# TSAL-GLV.net
KiCad netlist of a schematic drawn in EAGLE
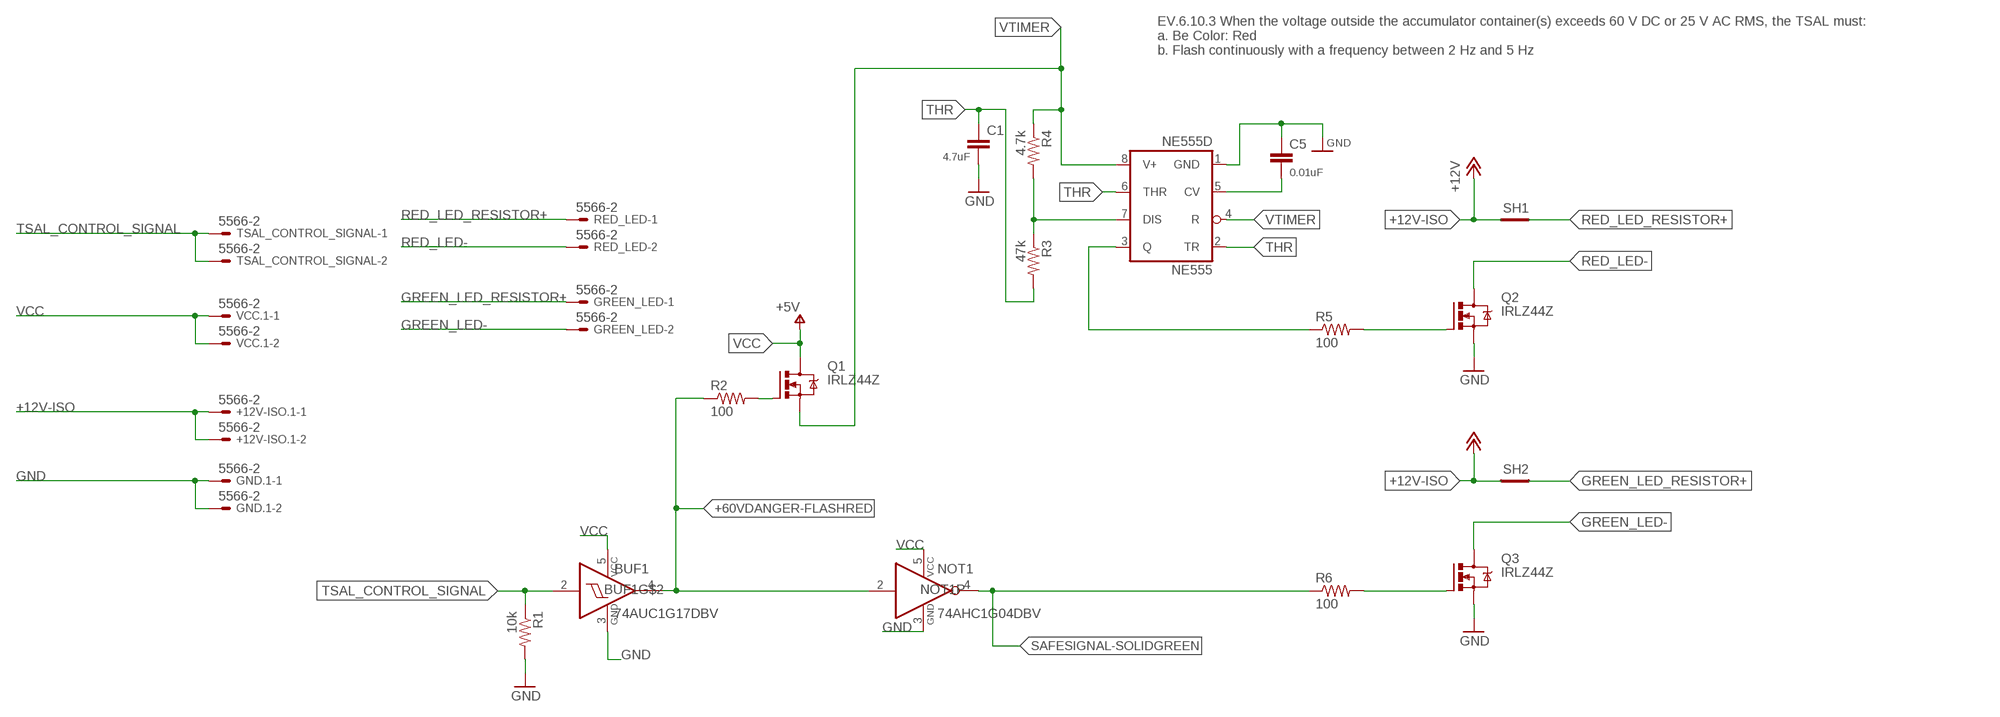
[diagram p0: schematic, sheet 1]

(export (version "E")
  (design (tool "Eeschema 10.0.6"))
  (components
    (comp (ref "+12V-ISO.1")
      (value "5566-2")
      (footprint "eagle-import:5566-2")
      (fields (field (name "MF") "MOLEX"))
      (libsource (lib "eagle-import") (part "5566-2"))
    )
    (comp (ref "BUF1")
      (value "74AUC1G17DBV")
      (footprint "eagle-import:SOT23-5")
      (libsource (lib "eagle-import") (part "741G17DBVAUC"))
    )
    (comp (ref "C1")
      (value "4.7uF")
      (footprint "eagle-import:C0805")
      (libsource (lib "eagle-import") (part "C-EUC0805"))
    )
    (comp (ref "C5")
      (value "0.01uF")
      (footprint "eagle-import:C0805")
      (libsource (lib "eagle-import") (part "C-EUC0805"))
    )
    (comp (ref "GND.1")
      (value "5566-2")
      (footprint "eagle-import:5566-2")
      (fields (field (name "MF") "MOLEX"))
      (libsource (lib "eagle-import") (part "5566-2"))
    )
    (comp (ref "GREEN_LED")
      (value "5566-2")
      (footprint "eagle-import:5566-2")
      (fields (field (name "MF") "MOLEX"))
      (libsource (lib "eagle-import") (part "5566-2"))
    )
    (comp (ref "NE555")
      (value "NE555D")
      (footprint "eagle-import:SO08")
      (libsource (lib "eagle-import") (part "555DNE"))
    )
    (comp (ref "NOT1")
      (value "74AHC1G04DBV")
      (footprint "eagle-import:SOT23-5")
      (libsource (lib "eagle-import") (part "741G04DBVAHC"))
    )
    (comp (ref "Q1")
      (value "IRLZ44Z")
      (footprint "eagle-import:TO220BH")
      (libsource (lib "eagle-import") (part "IRLZ44Z"))
    )
    (comp (ref "Q2")
      (value "IRLZ44Z")
      (footprint "eagle-import:TO220BH")
      (libsource (lib "eagle-import") (part "IRLZ44Z"))
    )
    (comp (ref "Q3")
      (value "IRLZ44Z")
      (footprint "eagle-import:TO220BH")
      (libsource (lib "eagle-import") (part "IRLZ44Z"))
    )
    (comp (ref "R1")
      (value "10k")
      (footprint "eagle-import:R0805")
      (libsource (lib "eagle-import") (part "R-US_R0805"))
    )
    (comp (ref "R2")
      (value "100")
      (footprint "eagle-import:R0805")
      (libsource (lib "eagle-import") (part "R-US_R0805"))
    )
    (comp (ref "R3")
      (value "47k")
      (footprint "eagle-import:R0805")
      (libsource (lib "eagle-import") (part "R-US_R0805"))
    )
    (comp (ref "R4")
      (value "4.7k")
      (footprint "eagle-import:R0805")
      (libsource (lib "eagle-import") (part "R-US_R0805"))
    )
    (comp (ref "R5")
      (value "100")
      (footprint "eagle-import:R0805")
      (libsource (lib "eagle-import") (part "R-US_R0805"))
    )
    (comp (ref "R6")
      (value "100")
      (footprint "eagle-import:R0805")
      (libsource (lib "eagle-import") (part "R-US_R0805"))
    )
    (comp (ref "RED_LED")
      (value "5566-2")
      (footprint "eagle-import:5566-2")
      (fields (field (name "MF") "MOLEX"))
      (libsource (lib "eagle-import") (part "5566-2"))
    )
    (comp (ref "SH1")
      (value "SHORTT5")
      (footprint "eagle-import:SHORT_TOP-50")
      (libsource (lib "eagle-import") (part "SHORTT5"))
    )
    (comp (ref "SH2")
      (value "SHORTT5")
      (footprint "eagle-import:SHORT_TOP-50")
      (libsource (lib "eagle-import") (part "SHORTT5"))
    )
    (comp (ref "TSAL_CONTROL_SIGNAL")
      (value "5566-2")
      (footprint "eagle-import:5566-2")
      (fields (field (name "MF") "MOLEX"))
      (libsource (lib "eagle-import") (part "5566-2"))
    )
    (comp (ref "VCC.1")
      (value "5566-2")
      (footprint "eagle-import:5566-2")
      (fields (field (name "MF") "MOLEX"))
      (libsource (lib "eagle-import") (part "5566-2"))
    )
  )
  (nets
    (net (code "1") (name "+12V-ISO") (class "Default")
      (node (ref "+12V-ISO.1") (pin "1") (pinfunction "S_1") (pintype "passive"))
      (node (ref "+12V-ISO.1") (pin "2") (pinfunction "S_2") (pintype "passive"))
      (node (ref "SH1") (pin "1") (pinfunction "P$1_1") (pintype "bidirectional"))
      (node (ref "SH2") (pin "1") (pinfunction "P$1_1") (pintype "bidirectional"))
    )
    (net (code "2") (name "+60VDANGER-FLASHRED") (class "Default")
      (node (ref "BUF1") (pin "4") (pinfunction "O_4") (pintype "output"))
      (node (ref "NOT1") (pin "2") (pinfunction "I_2") (pintype "input"))
      (node (ref "R2") (pin "1") (pinfunction "1_1") (pintype "passive"))
    )
    (net (code "3") (name "GND") (class "Default")
      (node (ref "BUF1") (pin "3") (pinfunction "GND_3") (pintype "power_in"))
      (node (ref "C1") (pin "2") (pinfunction "2_2") (pintype "passive"))
      (node (ref "C5") (pin "1") (pinfunction "1_1") (pintype "passive"))
      (node (ref "GND.1") (pin "1") (pinfunction "S_1") (pintype "passive"))
      (node (ref "GND.1") (pin "2") (pinfunction "S_2") (pintype "passive"))
      (node (ref "NE555") (pin "1") (pinfunction "GND_1") (pintype "power_in"))
      (node (ref "NOT1") (pin "3") (pinfunction "GND_3") (pintype "power_in"))
      (node (ref "Q2") (pin "S") (pinfunction "S_S") (pintype "passive"))
      (node (ref "Q3") (pin "S") (pinfunction "S_S") (pintype "passive"))
      (node (ref "R1") (pin "2") (pinfunction "2_2") (pintype "passive"))
    )
    (net (code "4") (name "GREEN_LED-") (class "Default")
      (node (ref "GREEN_LED") (pin "2") (pinfunction "S_2") (pintype "passive"))
      (node (ref "Q3") (pin "D") (pinfunction "D_D") (pintype "passive"))
    )
    (net (code "5") (name "GREEN_LED_RESISTOR+") (class "Default")
      (node (ref "GREEN_LED") (pin "1") (pinfunction "S_1") (pintype "passive"))
      (node (ref "SH2") (pin "2") (pinfunction "P$2_2") (pintype "bidirectional"))
    )
    (net (code "6") (name "Net-(NE555-CV)") (class "Default")
      (node (ref "C5") (pin "2") (pinfunction "2_2") (pintype "passive"))
      (node (ref "NE555") (pin "5") (pinfunction "CV_5") (pintype "input"))
    )
    (net (code "7") (name "Net-(NE555-DIS)") (class "Default")
      (node (ref "NE555") (pin "7") (pinfunction "DIS_7") (pintype "input"))
      (node (ref "R3") (pin "1") (pinfunction "1_1") (pintype "passive"))
      (node (ref "R4") (pin "2") (pinfunction "2_2") (pintype "passive"))
    )
    (net (code "8") (name "Net-(NE555-Q)") (class "Default")
      (node (ref "NE555") (pin "3") (pinfunction "Q_3") (pintype "output"))
      (node (ref "R5") (pin "1") (pinfunction "1_1") (pintype "passive"))
    )
    (net (code "9") (name "Net-(Q1-PadG)") (class "Default")
      (node (ref "Q1") (pin "G") (pinfunction "G_G") (pintype "passive"))
      (node (ref "R2") (pin "2") (pinfunction "2_2") (pintype "passive"))
    )
    (net (code "10") (name "Net-(Q2-PadG)") (class "Default")
      (node (ref "Q2") (pin "G") (pinfunction "G_G") (pintype "passive"))
      (node (ref "R5") (pin "2") (pinfunction "2_2") (pintype "passive"))
    )
    (net (code "11") (name "Net-(Q3-PadG)") (class "Default")
      (node (ref "Q3") (pin "G") (pinfunction "G_G") (pintype "passive"))
      (node (ref "R6") (pin "2") (pinfunction "2_2") (pintype "passive"))
    )
    (net (code "12") (name "RED_LED-") (class "Default")
      (node (ref "Q2") (pin "D") (pinfunction "D_D") (pintype "passive"))
      (node (ref "RED_LED") (pin "2") (pinfunction "S_2") (pintype "passive"))
    )
    (net (code "13") (name "RED_LED_RESISTOR+") (class "Default")
      (node (ref "RED_LED") (pin "1") (pinfunction "S_1") (pintype "passive"))
      (node (ref "SH1") (pin "2") (pinfunction "P$2_2") (pintype "bidirectional"))
    )
    (net (code "14") (name "SAFESIGNAL-SOLIDGREEN") (class "Default")
      (node (ref "NOT1") (pin "4") (pinfunction "O_4") (pintype "output"))
      (node (ref "R6") (pin "1") (pinfunction "1_1") (pintype "passive"))
    )
    (net (code "15") (name "THR") (class "Default")
      (node (ref "C1") (pin "1") (pinfunction "1_1") (pintype "passive"))
      (node (ref "NE555") (pin "2") (pinfunction "TR_2") (pintype "input"))
      (node (ref "NE555") (pin "6") (pinfunction "THR_6") (pintype "input"))
      (node (ref "R3") (pin "2") (pinfunction "2_2") (pintype "passive"))
    )
    (net (code "16") (name "TSAL_CONTROL_SIGNAL") (class "Default")
      (node (ref "BUF1") (pin "2") (pinfunction "I_2") (pintype "input"))
      (node (ref "R1") (pin "1") (pinfunction "1_1") (pintype "passive"))
      (node (ref "TSAL_CONTROL_SIGNAL") (pin "1") (pinfunction "S_1") (pintype "passive"))
      (node (ref "TSAL_CONTROL_SIGNAL") (pin "2") (pinfunction "S_2") (pintype "passive"))
    )
    (net (code "17") (name "VCC") (class "Default")
      (node (ref "BUF1") (pin "5") (pinfunction "VCC_5") (pintype "power_in"))
      (node (ref "NOT1") (pin "5") (pinfunction "VCC_5") (pintype "power_in"))
      (node (ref "Q1") (pin "D") (pinfunction "D_D") (pintype "passive"))
      (node (ref "VCC.1") (pin "1") (pinfunction "S_1") (pintype "passive"))
      (node (ref "VCC.1") (pin "2") (pinfunction "S_2") (pintype "passive"))
    )
    (net (code "18") (name "VTIMER") (class "Default")
      (node (ref "NE555") (pin "4") (pinfunction "R_4") (pintype "input"))
      (node (ref "NE555") (pin "8") (pinfunction "V+_8") (pintype "power_in"))
      (node (ref "Q1") (pin "S") (pinfunction "S_S") (pintype "passive"))
      (node (ref "R4") (pin "1") (pinfunction "1_1") (pintype "passive"))
    )
  )
)
